# Adafruit_2_9in_eInk_Display.net
KiCad netlist of a schematic drawn in EAGLE
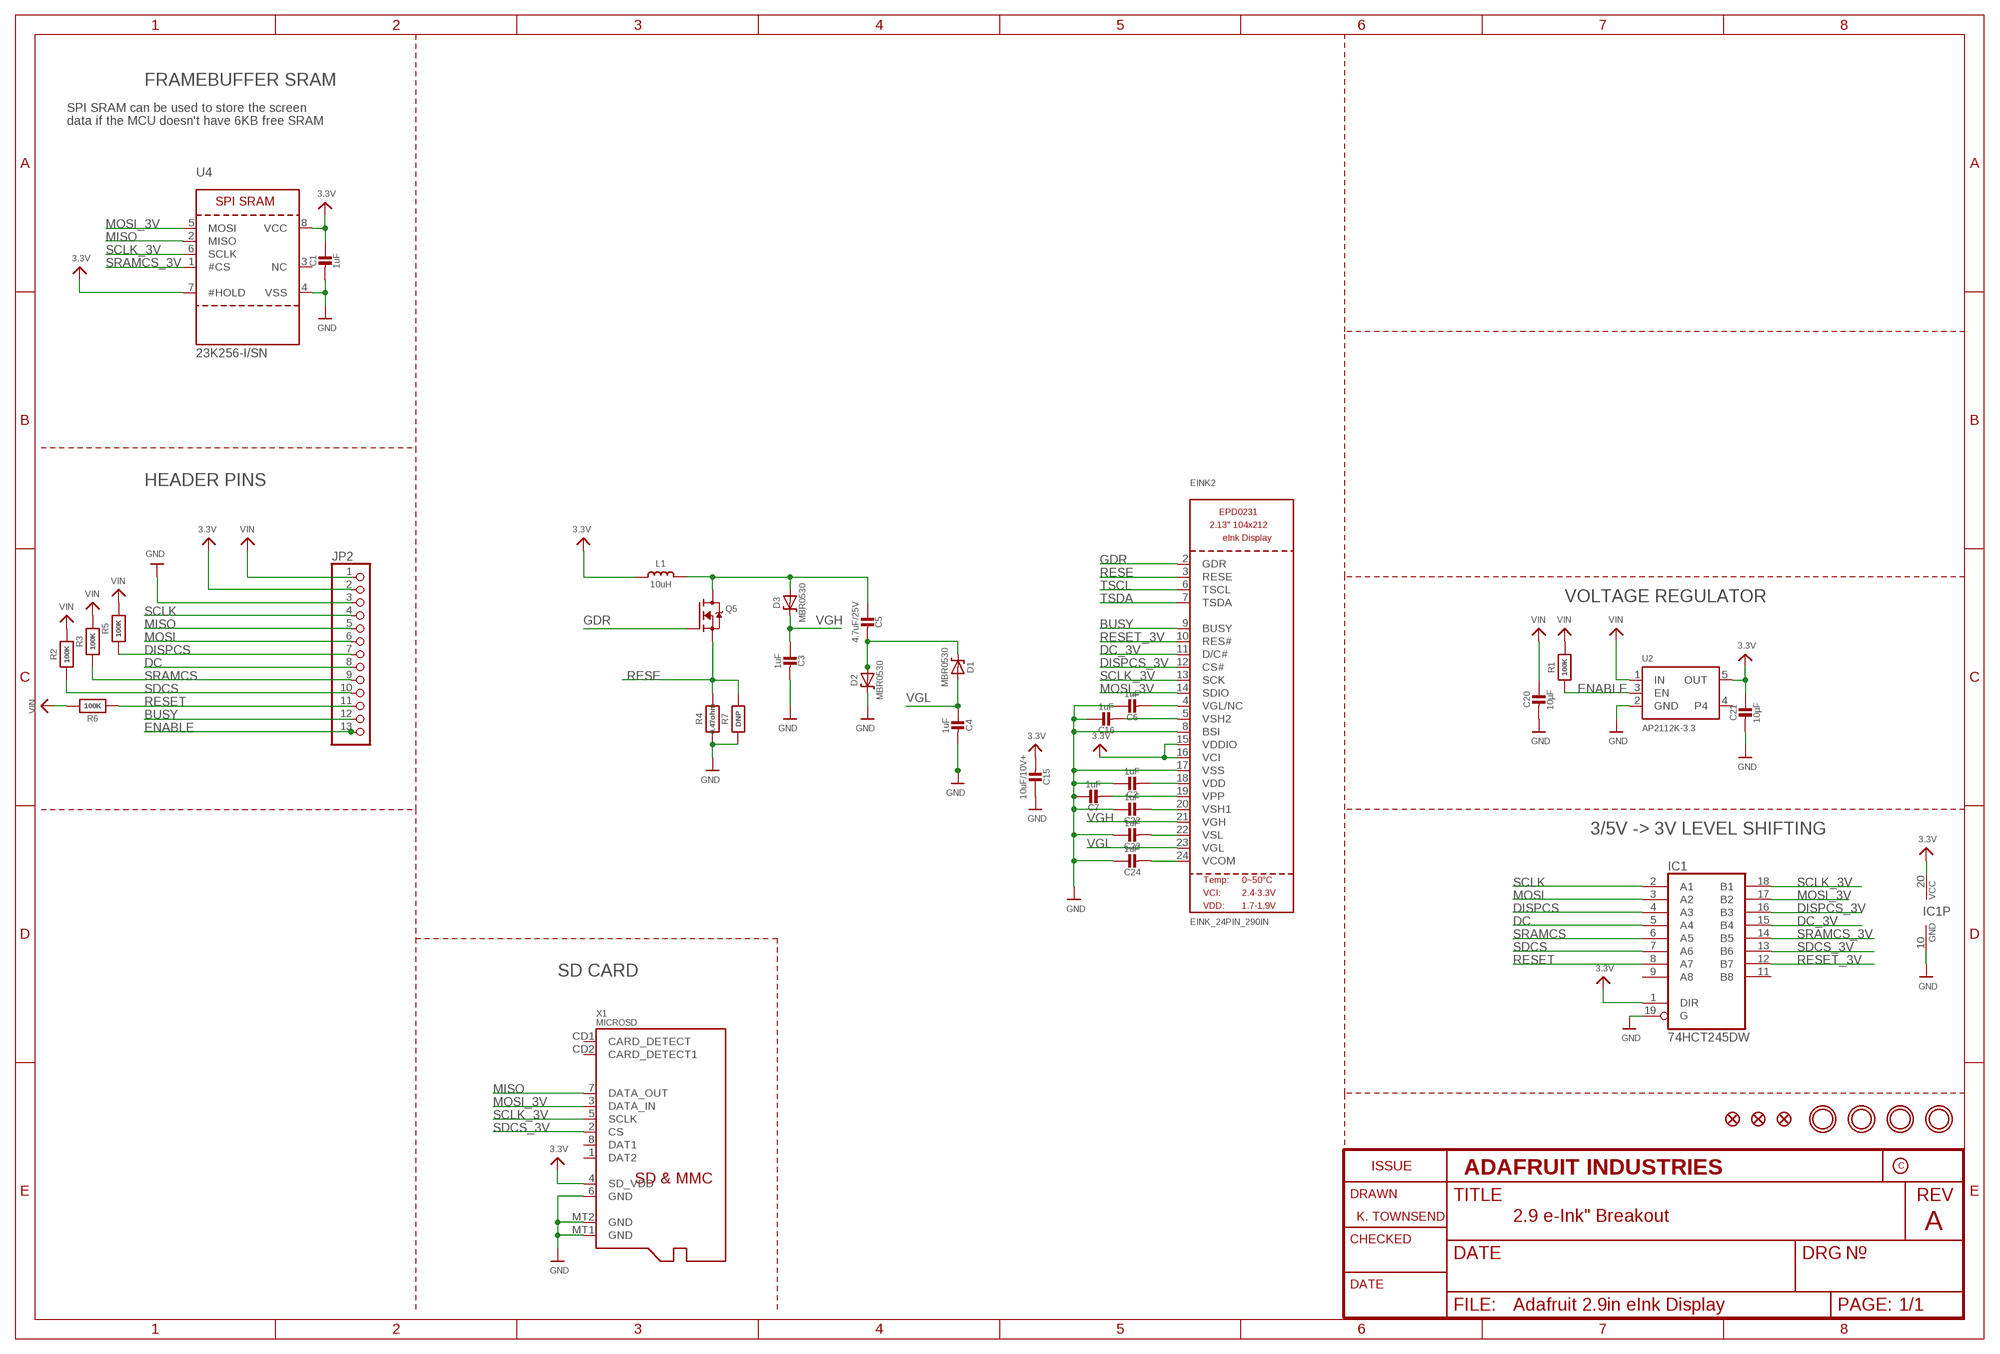
[diagram p0: schematic, sheet 1]

(export (version "E")
  (design (tool "Eeschema 10.0.6"))
  (components
    (comp (ref "C1")
      (value "1uF")
      (footprint "eagle-import:0805_10MGAP")
      (libsource (lib "eagle-import") (part "CAP_CERAMIC0805_10MGAP"))
    )
    (comp (ref "C2")
      (value "1uF")
      (footprint "eagle-import:0805-NO")
      (libsource (lib "eagle-import") (part "CAP_CERAMIC0805-NOOUTLINE"))
    )
    (comp (ref "C3")
      (value "1uF")
      (footprint "eagle-import:0805-NO")
      (libsource (lib "eagle-import") (part "CAP_CERAMIC0805-NOOUTLINE"))
    )
    (comp (ref "C4")
      (value "1uF")
      (footprint "eagle-import:0805-NO")
      (libsource (lib "eagle-import") (part "CAP_CERAMIC0805-NOOUTLINE"))
    )
    (comp (ref "C5")
      (value "4.7uF/25V")
      (footprint "eagle-import:0805-NO")
      (libsource (lib "eagle-import") (part "CAP_CERAMIC0805-NOOUTLINE"))
    )
    (comp (ref "C6")
      (value "1uF")
      (footprint "eagle-import:0805-NO")
      (libsource (lib "eagle-import") (part "CAP_CERAMIC0805-NOOUTLINE"))
    )
    (comp (ref "C7")
      (value "1uF")
      (footprint "eagle-import:0805-NO")
      (libsource (lib "eagle-import") (part "CAP_CERAMIC0805-NOOUTLINE"))
    )
    (comp (ref "C15")
      (value "10uF/10V+")
      (footprint "eagle-import:0805-NO")
      (libsource (lib "eagle-import") (part "CAP_CERAMIC0805-NOOUTLINE"))
    )
    (comp (ref "C16")
      (value "1uF")
      (footprint "eagle-import:0805-NO")
      (libsource (lib "eagle-import") (part "CAP_CERAMIC0805-NOOUTLINE"))
    )
    (comp (ref "C20")
      (value "10µF")
      (footprint "eagle-import:0805-NO")
      (libsource (lib "eagle-import") (part "CAP_CERAMIC0805-NOOUTLINE"))
    )
    (comp (ref "C21")
      (value "10µF")
      (footprint "eagle-import:0805-NO")
      (libsource (lib "eagle-import") (part "CAP_CERAMIC0805-NOOUTLINE"))
    )
    (comp (ref "C22")
      (value "1uF")
      (footprint "eagle-import:0805-NO")
      (libsource (lib "eagle-import") (part "CAP_CERAMIC0805-NOOUTLINE"))
    )
    (comp (ref "C23")
      (value "1uF")
      (footprint "eagle-import:0805-NO")
      (libsource (lib "eagle-import") (part "CAP_CERAMIC0805-NOOUTLINE"))
    )
    (comp (ref "C24")
      (value "1uF")
      (footprint "eagle-import:0805-NO")
      (libsource (lib "eagle-import") (part "CAP_CERAMIC0805-NOOUTLINE"))
    )
    (comp (ref "D1")
      (value "MBR0530")
      (footprint "eagle-import:SOD-123")
      (libsource (lib "eagle-import") (part "DIODE-SCHOTTKYSOD-123"))
    )
    (comp (ref "D2")
      (value "MBR0530")
      (footprint "eagle-import:SOD-123")
      (libsource (lib "eagle-import") (part "DIODE-SCHOTTKYSOD-123"))
    )
    (comp (ref "D3")
      (value "MBR0530")
      (footprint "eagle-import:SOD-123")
      (libsource (lib "eagle-import") (part "DIODE-SCHOTTKYSOD-123"))
    )
    (comp (ref "EINK2")
      (value "EINK_24PIN_290IN")
      (footprint "eagle-import:EINK_290IN")
      (libsource (lib "eagle-import") (part "EINK_24PIN_290IN"))
    )
    (comp (ref "FID1")
      (value "FIDUCIAL_1MM")
      (footprint "eagle-import:FIDUCIAL_1MM")
      (libsource (lib "eagle-import") (part "FIDUCIAL_1MM"))
    )
    (comp (ref "FID2")
      (value "FIDUCIAL_1MM")
      (footprint "eagle-import:FIDUCIAL_1MM")
      (libsource (lib "eagle-import") (part "FIDUCIAL_1MM"))
    )
    (comp (ref "FID3")
      (value "FIDUCIAL_1MM")
      (footprint "eagle-import:FIDUCIAL_1MM")
      (libsource (lib "eagle-import") (part "FIDUCIAL_1MM"))
    )
    (comp (ref "IC1")
      (value "74HCT245DW")
      (footprint "eagle-import:SO20W")
      (libsource (lib "eagle-import") (part "74245DWHCT"))
    )
    (comp (ref "JP2")
      (value "HEADER-1X13")
      (footprint "eagle-import:1X13_ROUND_70")
      (libsource (lib "eagle-import") (part "HEADER-1X13"))
    )
    (comp (ref "L1")
      (value "10uH")
      (footprint "eagle-import:INDUCTOR_4X4MM_NR401")
      (libsource (lib "eagle-import") (part "INDUCTORNR401"))
    )
    (comp (ref "Q5")
      (value "IRLML0100")
      (footprint "eagle-import:SOT23-3")
      (libsource (lib "eagle-import") (part "IRLML2060TRPBF"))
    )
    (comp (ref "R1")
      (value "100K")
      (footprint "eagle-import:0805-NO")
      (libsource (lib "eagle-import") (part "RESISTOR0805_NOOUTLINE"))
    )
    (comp (ref "R2")
      (value "100K")
      (footprint "eagle-import:0805-NO")
      (libsource (lib "eagle-import") (part "RESISTOR0805_NOOUTLINE"))
    )
    (comp (ref "R3")
      (value "100K")
      (footprint "eagle-import:0805-NO")
      (libsource (lib "eagle-import") (part "RESISTOR0805_NOOUTLINE"))
    )
    (comp (ref "R4")
      (value "0.47ohm")
      (footprint "eagle-import:0805_10MGAP")
      (libsource (lib "eagle-import") (part "RESISTOR0805_10MGAP"))
    )
    (comp (ref "R5")
      (value "100K")
      (footprint "eagle-import:0805-NO")
      (libsource (lib "eagle-import") (part "RESISTOR0805_NOOUTLINE"))
    )
    (comp (ref "R6")
      (value "100K")
      (footprint "eagle-import:0805-NO")
      (libsource (lib "eagle-import") (part "RESISTOR0805_NOOUTLINE"))
    )
    (comp (ref "R7")
      (value "DNP")
      (footprint "eagle-import:0805_10MGAP")
      (libsource (lib "eagle-import") (part "RESISTOR0805_10MGAP"))
    )
    (comp (ref "U$3")
      (value "MOUNTINGHOLE2.5")
      (footprint "eagle-import:MOUNTINGHOLE_2.5_PLATED")
      (libsource (lib "eagle-import") (part "MOUNTINGHOLE2.5"))
    )
    (comp (ref "U$4")
      (value "MOUNTINGHOLE2.5")
      (footprint "eagle-import:MOUNTINGHOLE_2.5_PLATED")
      (libsource (lib "eagle-import") (part "MOUNTINGHOLE2.5"))
    )
    (comp (ref "U$5")
      (value "MOUNTINGHOLE2.5")
      (footprint "eagle-import:MOUNTINGHOLE_2.5_PLATED")
      (libsource (lib "eagle-import") (part "MOUNTINGHOLE2.5"))
    )
    (comp (ref "U$6")
      (value "MOUNTINGHOLE2.5")
      (footprint "eagle-import:MOUNTINGHOLE_2.5_PLATED")
      (libsource (lib "eagle-import") (part "MOUNTINGHOLE2.5"))
    )
    (comp (ref "U2")
      (value "AP2112K-3.3")
      (footprint "eagle-import:SOT23-5")
      (libsource (lib "eagle-import") (part "VREG_SOT23-5"))
    )
    (comp (ref "U4")
      (value "23K256-I/SN")
      (footprint "eagle-import:SOIC8_150MIL")
      (libsource (lib "eagle-import") (part "SRAM_SPI_SOIC8"))
    )
    (comp (ref "X1")
      (value "MICROSD")
      (footprint "eagle-import:MICROSD")
      (libsource (lib "eagle-import") (part "MICROSD"))
    )
  )
  (nets
    (net (code "1") (name "/BUSY") (class "Default")
      (node (ref "EINK2") (pin "9") (pinfunction "BUSY_9") (pintype "output"))
      (node (ref "JP2") (pin "12") (pinfunction "12_12") (pintype "passive"))
    )
    (net (code "2") (name "/DC") (class "Default")
      (node (ref "IC1") (pin "5") (pinfunction "A4_5") (pintype "bidirectional"))
      (node (ref "JP2") (pin "8") (pinfunction "8_8") (pintype "passive"))
    )
    (net (code "3") (name "/DC_3V") (class "Default")
      (node (ref "EINK2") (pin "11") (pinfunction "D/C#_11") (pintype "input"))
      (node (ref "IC1") (pin "15") (pinfunction "B4_15") (pintype "bidirectional"))
    )
    (net (code "4") (name "/DISPCS") (class "Default")
      (node (ref "IC1") (pin "4") (pinfunction "A3_4") (pintype "bidirectional"))
      (node (ref "JP2") (pin "7") (pinfunction "7_7") (pintype "passive"))
      (node (ref "R5") (pin "1") (pinfunction "1_1") (pintype "passive"))
    )
    (net (code "5") (name "/DISPCS_3V") (class "Default")
      (node (ref "EINK2") (pin "12") (pinfunction "CS#_12") (pintype "input"))
      (node (ref "IC1") (pin "16") (pinfunction "B3_16") (pintype "bidirectional"))
    )
    (net (code "6") (name "/ENABLE") (class "Default")
      (node (ref "JP2") (pin "13") (pinfunction "13_13") (pintype "passive"))
      (node (ref "R1") (pin "1") (pinfunction "1_1") (pintype "passive"))
      (node (ref "U2") (pin "3") (pinfunction "EN_3") (pintype "input"))
    )
    (net (code "7") (name "/GDR") (class "Default")
      (node (ref "EINK2") (pin "2") (pinfunction "GDR_2") (pintype "output"))
      (node (ref "Q5") (pin "1") (pinfunction "G_1") (pintype "bidirectional"))
    )
    (net (code "8") (name "/MISO") (class "Default")
      (node (ref "JP2") (pin "5") (pinfunction "5_5") (pintype "passive"))
      (node (ref "U4") (pin "2") (pinfunction "MISO_2") (pintype "output"))
      (node (ref "X1") (pin "7") (pinfunction "DATA_OUT_7") (pintype "output"))
    )
    (net (code "9") (name "/MOSI") (class "Default")
      (node (ref "IC1") (pin "3") (pinfunction "A2_3") (pintype "bidirectional"))
      (node (ref "JP2") (pin "6") (pinfunction "6_6") (pintype "passive"))
    )
    (net (code "10") (name "/MOSI_3V") (class "Default")
      (node (ref "EINK2") (pin "14") (pinfunction "SDIO_14") (pintype "bidirectional"))
      (node (ref "IC1") (pin "17") (pinfunction "B2_17") (pintype "bidirectional"))
      (node (ref "U4") (pin "5") (pinfunction "MOSI_5") (pintype "input"))
      (node (ref "X1") (pin "3") (pinfunction "DATA_IN_3") (pintype "input"))
    )
    (net (code "11") (name "/RESE") (class "Default")
      (node (ref "EINK2") (pin "3") (pinfunction "RESE_3") (pintype "input"))
      (node (ref "Q5") (pin "2") (pinfunction "S_2") (pintype "bidirectional"))
      (node (ref "R4") (pin "1") (pinfunction "1_1") (pintype "passive"))
      (node (ref "R7") (pin "1") (pinfunction "1_1") (pintype "passive"))
    )
    (net (code "12") (name "/RESET") (class "Default")
      (node (ref "IC1") (pin "8") (pinfunction "A7_8") (pintype "bidirectional"))
      (node (ref "JP2") (pin "11") (pinfunction "11_11") (pintype "passive"))
      (node (ref "R6") (pin "1") (pinfunction "1_1") (pintype "passive"))
    )
    (net (code "13") (name "/RESET_3V") (class "Default")
      (node (ref "EINK2") (pin "10") (pinfunction "RES#_10") (pintype "input"))
      (node (ref "IC1") (pin "12") (pinfunction "B7_12") (pintype "bidirectional"))
    )
    (net (code "14") (name "/SCLK") (class "Default")
      (node (ref "IC1") (pin "2") (pinfunction "A1_2") (pintype "bidirectional"))
      (node (ref "JP2") (pin "4") (pinfunction "4_4") (pintype "passive"))
    )
    (net (code "15") (name "/SCLK_3V") (class "Default")
      (node (ref "EINK2") (pin "13") (pinfunction "SCK_13") (pintype "bidirectional"))
      (node (ref "IC1") (pin "18") (pinfunction "B1_18") (pintype "bidirectional"))
      (node (ref "U4") (pin "6") (pinfunction "SCLK_6") (pintype "input"))
      (node (ref "X1") (pin "5") (pinfunction "SCLK_5") (pintype "input"))
    )
    (net (code "16") (name "/SDCS") (class "Default")
      (node (ref "IC1") (pin "7") (pinfunction "A6_7") (pintype "bidirectional"))
      (node (ref "JP2") (pin "10") (pinfunction "10_10") (pintype "passive"))
      (node (ref "R2") (pin "1") (pinfunction "1_1") (pintype "passive"))
    )
    (net (code "17") (name "/SDCS_3V") (class "Default")
      (node (ref "IC1") (pin "13") (pinfunction "B6_13") (pintype "bidirectional"))
      (node (ref "X1") (pin "2") (pinfunction "CS_2") (pintype "input"))
    )
    (net (code "18") (name "/SRAMCS") (class "Default")
      (node (ref "IC1") (pin "6") (pinfunction "A5_6") (pintype "bidirectional"))
      (node (ref "JP2") (pin "9") (pinfunction "9_9") (pintype "passive"))
      (node (ref "R3") (pin "1") (pinfunction "1_1") (pintype "passive"))
    )
    (net (code "19") (name "/SRAMCS_3V") (class "Default")
      (node (ref "IC1") (pin "14") (pinfunction "B5_14") (pintype "bidirectional"))
      (node (ref "U4") (pin "1") (pinfunction "#CS_1") (pintype "input"))
    )
    (net (code "20") (name "/TSCL") (class "Default")
      (node (ref "EINK2") (pin "6") (pinfunction "TSCL_6") (pintype "output"))
    )
    (net (code "21") (name "/TSDA") (class "Default")
      (node (ref "EINK2") (pin "7") (pinfunction "TSDA_7") (pintype "bidirectional"))
    )
    (net (code "22") (name "/VGH") (class "Default")
      (node (ref "C3") (pin "1") (pinfunction "1_1") (pintype "passive"))
      (node (ref "D3") (pin "C") (pinfunction "C_C") (pintype "passive"))
      (node (ref "EINK2") (pin "21") (pinfunction "VGH_21") (pintype "passive"))
    )
    (net (code "23") (name "/VGL") (class "Default")
      (node (ref "C4") (pin "1") (pinfunction "1_1") (pintype "passive"))
      (node (ref "D1") (pin "A") (pinfunction "A_A") (pintype "passive"))
      (node (ref "EINK2") (pin "23") (pinfunction "VGL_23") (pintype "passive"))
    )
    (net (code "24") (name "3.3V") (class "Default")
      (node (ref "C1") (pin "1") (pinfunction "1_1") (pintype "passive"))
      (node (ref "C15") (pin "2") (pinfunction "2_2") (pintype "passive"))
      (node (ref "C21") (pin "1") (pinfunction "1_1") (pintype "passive"))
      (node (ref "EINK2") (pin "15") (pinfunction "VDDIO_15") (pintype "power_in"))
      (node (ref "EINK2") (pin "16") (pinfunction "VCI_16") (pintype "power_in"))
      (node (ref "IC1") (pin "1") (pinfunction "DIR_1") (pintype "input"))
      (node (ref "IC1") (pin "20") (pinfunction "VCC_20") (pintype "power_in"))
      (node (ref "JP2") (pin "2") (pinfunction "2_2") (pintype "passive"))
      (node (ref "L1") (pin "P$2") (pinfunction "2_P$2") (pintype "passive"))
      (node (ref "U2") (pin "5") (pinfunction "OUT_5") (pintype "power_in"))
      (node (ref "U4") (pin "7") (pinfunction "#HOLD_7") (pintype "input"))
      (node (ref "U4") (pin "8") (pinfunction "VCC_8") (pintype "power_in"))
      (node (ref "X1") (pin "4") (pinfunction "SD_VDD_4") (pintype "power_in"))
    )
    (net (code "25") (name "GND") (class "Default")
      (node (ref "C1") (pin "2") (pinfunction "2_2") (pintype "passive"))
      (node (ref "C15") (pin "1") (pinfunction "1_1") (pintype "passive"))
      (node (ref "C16") (pin "1") (pinfunction "1_1") (pintype "passive"))
      (node (ref "C2") (pin "1") (pinfunction "1_1") (pintype "passive"))
      (node (ref "C20") (pin "2") (pinfunction "2_2") (pintype "passive"))
      (node (ref "C21") (pin "2") (pinfunction "2_2") (pintype "passive"))
      (node (ref "C22") (pin "1") (pinfunction "1_1") (pintype "passive"))
      (node (ref "C23") (pin "1") (pinfunction "1_1") (pintype "passive"))
      (node (ref "C24") (pin "1") (pinfunction "1_1") (pintype "passive"))
      (node (ref "C3") (pin "2") (pinfunction "2_2") (pintype "passive"))
      (node (ref "C4") (pin "2") (pinfunction "2_2") (pintype "passive"))
      (node (ref "C6") (pin "1") (pinfunction "1_1") (pintype "passive"))
      (node (ref "C7") (pin "1") (pinfunction "1_1") (pintype "passive"))
      (node (ref "D2") (pin "C") (pinfunction "C_C") (pintype "passive"))
      (node (ref "EINK2") (pin "17") (pinfunction "VSS_17") (pintype "power_in"))
      (node (ref "EINK2") (pin "8") (pinfunction "BSI_8") (pintype "input"))
      (node (ref "IC1") (pin "10") (pinfunction "GND_10") (pintype "power_in"))
      (node (ref "IC1") (pin "19") (pinfunction "G_19") (pintype "input"))
      (node (ref "JP2") (pin "3") (pinfunction "3_3") (pintype "passive"))
      (node (ref "R4") (pin "2") (pinfunction "2_2") (pintype "passive"))
      (node (ref "R7") (pin "2") (pinfunction "2_2") (pintype "passive"))
      (node (ref "U2") (pin "2") (pinfunction "GND_2") (pintype "power_in"))
      (node (ref "U4") (pin "4") (pinfunction "VSS_4") (pintype "power_in"))
      (node (ref "X1") (pin "6") (pinfunction "GND_6") (pintype "power_in"))
      (node (ref "X1") (pin "MT1") (pinfunction "GND_MT1") (pintype "power_in"))
      (node (ref "X1") (pin "MT2") (pinfunction "GND_MT2") (pintype "power_in"))
    )
    (net (code "26") (name "Net-(C5-Pad2)") (class "Default")
      (node (ref "C5") (pin "2") (pinfunction "2_2") (pintype "passive"))
      (node (ref "D1") (pin "C") (pinfunction "C_C") (pintype "passive"))
      (node (ref "D2") (pin "A") (pinfunction "A_A") (pintype "passive"))
    )
    (net (code "27") (name "Net-(EINK2-VCOM)") (class "Default")
      (node (ref "C24") (pin "2") (pinfunction "2_2") (pintype "passive"))
      (node (ref "EINK2") (pin "24") (pinfunction "VCOM_24") (pintype "passive"))
    )
    (net (code "28") (name "Net-(EINK2-VDD)") (class "Default")
      (node (ref "C2") (pin "2") (pinfunction "2_2") (pintype "passive"))
      (node (ref "EINK2") (pin "18") (pinfunction "VDD_18") (pintype "passive"))
    )
    (net (code "29") (name "Net-(EINK2-VGL{slash}NC)") (class "Default")
      (node (ref "C6") (pin "2") (pinfunction "2_2") (pintype "passive"))
      (node (ref "EINK2") (pin "4") (pinfunction "VGL/NC_4") (pintype "bidirectional"))
    )
    (net (code "30") (name "Net-(EINK2-VPP)") (class "Default")
      (node (ref "C7") (pin "2") (pinfunction "2_2") (pintype "passive"))
      (node (ref "EINK2") (pin "19") (pinfunction "VPP_19") (pintype "passive"))
    )
    (net (code "31") (name "Net-(EINK2-VSH1)") (class "Default")
      (node (ref "C22") (pin "2") (pinfunction "2_2") (pintype "passive"))
      (node (ref "EINK2") (pin "20") (pinfunction "VSH1_20") (pintype "passive"))
    )
    (net (code "32") (name "Net-(EINK2-VSH2)") (class "Default")
      (node (ref "C16") (pin "2") (pinfunction "2_2") (pintype "passive"))
      (node (ref "EINK2") (pin "5") (pinfunction "VSH2_5") (pintype "passive"))
    )
    (net (code "33") (name "Net-(EINK2-VSL)") (class "Default")
      (node (ref "C23") (pin "2") (pinfunction "2_2") (pintype "passive"))
      (node (ref "EINK2") (pin "22") (pinfunction "VSL_22") (pintype "passive"))
    )
    (net (code "34") (name "Net-(L1-1)") (class "Default")
      (node (ref "C5") (pin "1") (pinfunction "1_1") (pintype "passive"))
      (node (ref "D3") (pin "A") (pinfunction "A_A") (pintype "passive"))
      (node (ref "L1") (pin "P$1") (pinfunction "1_P$1") (pintype "passive"))
      (node (ref "Q5") (pin "3") (pinfunction "D_3") (pintype "bidirectional"))
    )
    (net (code "35") (name "VIN") (class "Default")
      (node (ref "C20") (pin "1") (pinfunction "1_1") (pintype "passive"))
      (node (ref "JP2") (pin "1") (pinfunction "1_1") (pintype "passive"))
      (node (ref "R1") (pin "2") (pinfunction "2_2") (pintype "passive"))
      (node (ref "R2") (pin "2") (pinfunction "2_2") (pintype "passive"))
      (node (ref "R3") (pin "2") (pinfunction "2_2") (pintype "passive"))
      (node (ref "R5") (pin "2") (pinfunction "2_2") (pintype "passive"))
      (node (ref "R6") (pin "2") (pinfunction "2_2") (pintype "passive"))
      (node (ref "U2") (pin "1") (pinfunction "IN_1") (pintype "power_in"))
    )
    (net (code "36") (name "unconnected-(IC1A-A8-Pad9)") (class "Default")
      (node (ref "IC1") (pin "9") (pinfunction "A8_9") (pintype "bidirectional"))
    )
    (net (code "37") (name "unconnected-(IC1A-B8-Pad11)") (class "Default")
      (node (ref "IC1") (pin "11") (pinfunction "B8_11") (pintype "bidirectional"))
    )
    (net (code "38") (name "unconnected-(U2-P4-Pad4)") (class "Default")
      (node (ref "U2") (pin "4") (pinfunction "P4_4") (pintype "bidirectional"))
    )
    (net (code "39") (name "unconnected-(U4-NC-Pad3)") (class "Default")
      (node (ref "U4") (pin "3") (pinfunction "NC_3") (pintype "no_connect"))
    )
    (net (code "40") (name "unconnected-(X1-CARD_DETECT-PadCD1)") (class "Default")
      (node (ref "X1") (pin "CD1") (pinfunction "CARD_DETECT_CD1") (pintype "passive"))
    )
    (net (code "41") (name "unconnected-(X1-CARD_DETECT1-PadCD2)") (class "Default")
      (node (ref "X1") (pin "CD2") (pinfunction "CARD_DETECT1_CD2") (pintype "passive"))
    )
    (net (code "42") (name "unconnected-(X1-DAT1-Pad8)") (class "Default")
      (node (ref "X1") (pin "8") (pinfunction "DAT1_8") (pintype "bidirectional"))
    )
    (net (code "43") (name "unconnected-(X1-DAT2-Pad1)") (class "Default")
      (node (ref "X1") (pin "1") (pinfunction "DAT2_1") (pintype "bidirectional"))
    )
  )
)
